# tutorial3.net
KiCad netlist of a schematic drawn in EAGLE
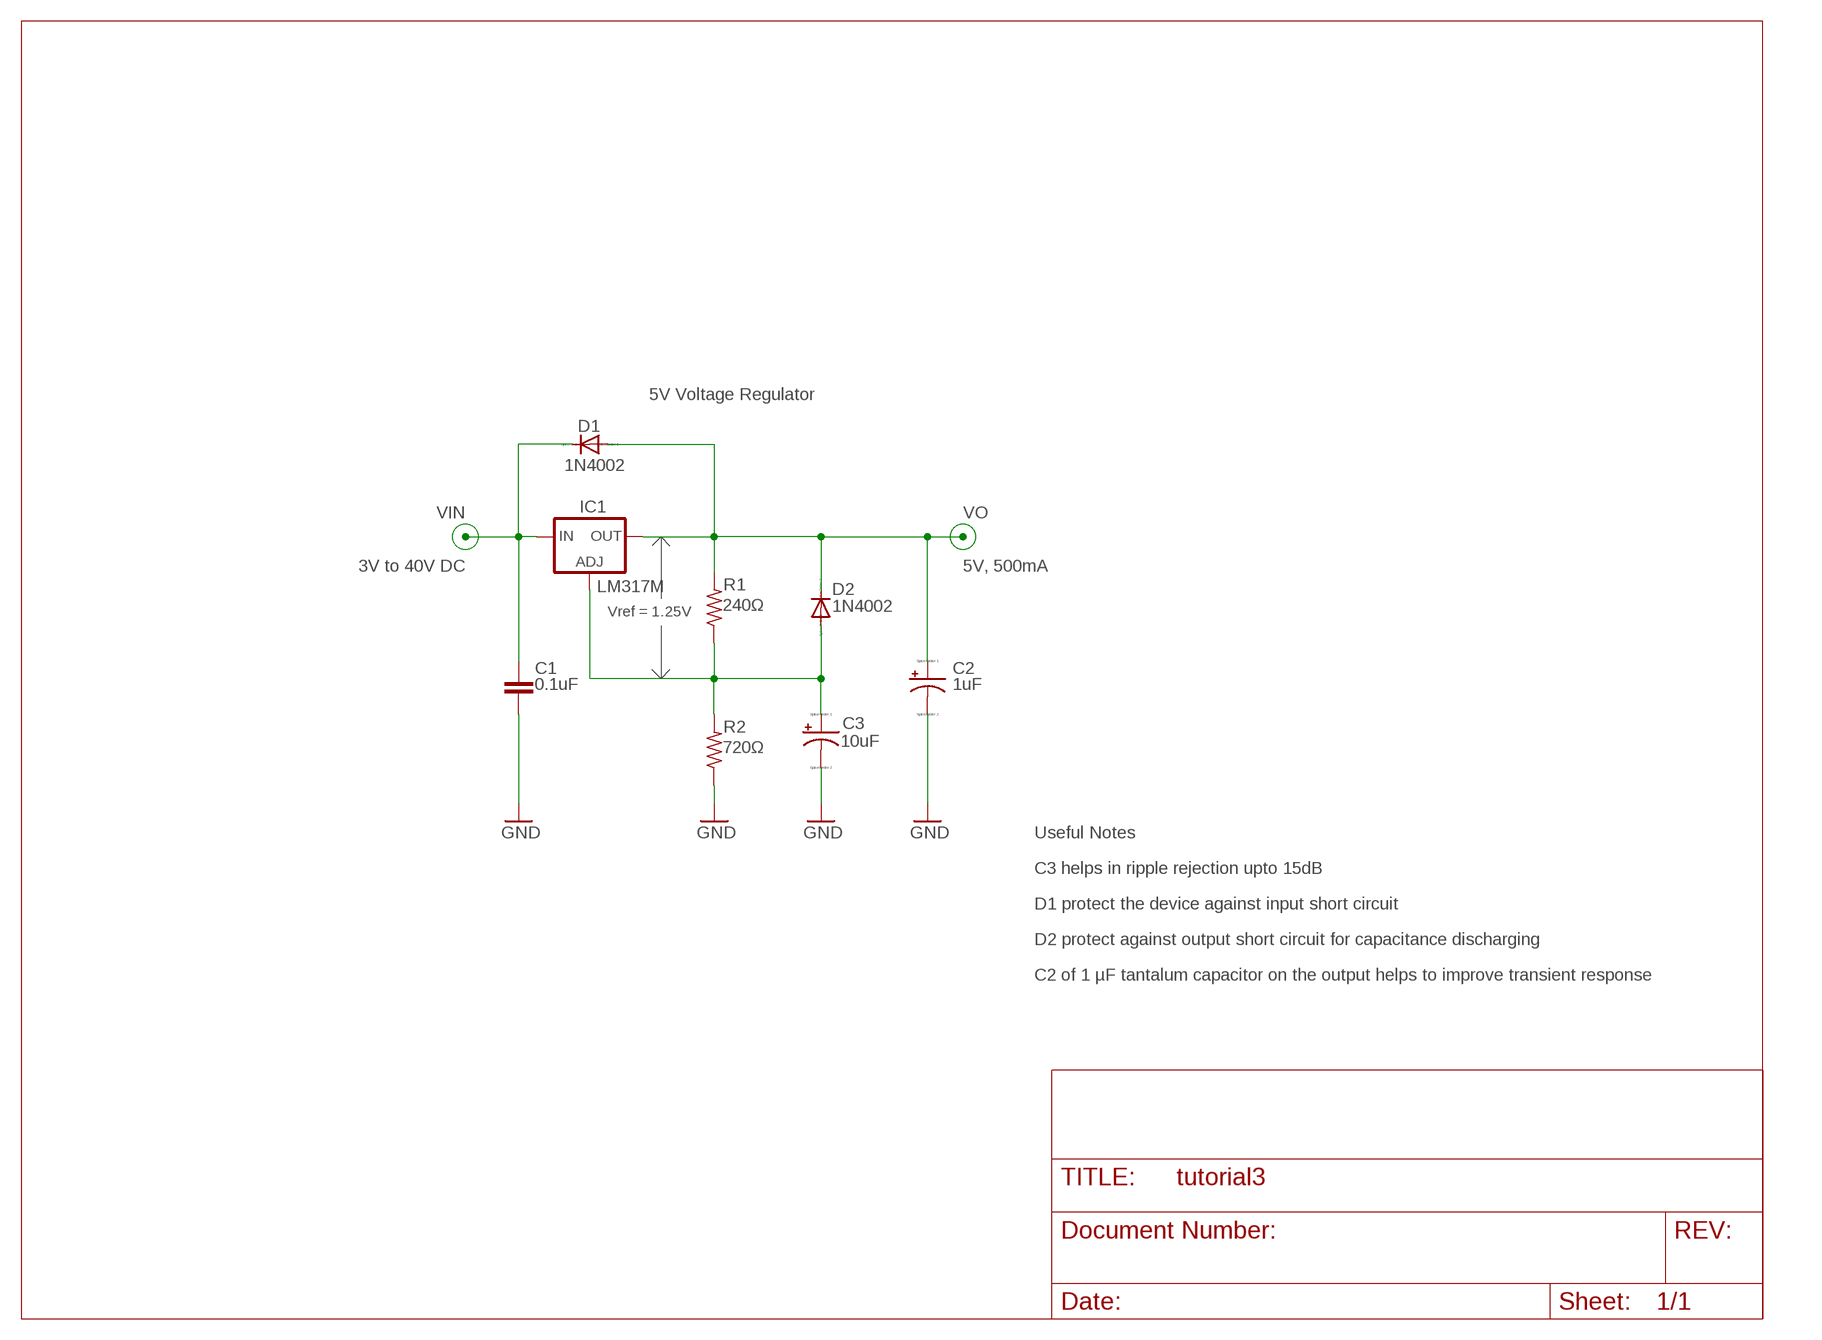
[diagram p0: schematic, sheet 1]

(export (version "E")
  (design (tool "Eeschema 10.0.6"))
  (components
    (comp (ref "C1")
      (value "0.1uF")
      (footprint "eagle-import:C075-052X106")
      (libsource (lib "eagle-import") (part "C-EU075-052X106"))
    )
    (comp (ref "C2")
      (value "1uF")
      (footprint "eagle-import:085CS_1AR")
      (libsource (lib "eagle-import") (part "CPOL-US085CS-1AR"))
    )
    (comp (ref "C3")
      (value "10uF")
      (footprint "eagle-import:085CS_1AR")
      (libsource (lib "eagle-import") (part "CPOL-US085CS-1AR"))
    )
    (comp (ref "D1")
      (value "1N4002")
      (footprint "eagle-import:DO41-10")
      (libsource (lib "eagle-import") (part "1N4004"))
    )
    (comp (ref "D2")
      (value "1N4002")
      (footprint "eagle-import:DO41-10")
      (libsource (lib "eagle-import") (part "1N4004"))
    )
    (comp (ref "IC1")
      (value "LM317MBSTT3")
      (footprint "eagle-import:SOT223")
      (fields (field (name "PARTNUMBER") "LM317M"))
      (libsource (lib "eagle-import") (part "LM317?MBSTT3"))
    )
    (comp (ref "R1")
      (value "240Ω")
      (footprint "eagle-import:M0805")
      (libsource (lib "eagle-import") (part "R-US_M0805"))
    )
    (comp (ref "R2")
      (value "720Ω")
      (footprint "eagle-import:M0805")
      (libsource (lib "eagle-import") (part "R-US_M0805"))
    )
  )
  (nets
    (net (code "1") (name "/VIN") (class "Default")
      (node (ref "C1") (pin "1") (pinfunction "1_1") (pintype "passive"))
      (node (ref "D1") (pin "C") (pinfunction "C_C") (pintype "passive"))
      (node (ref "IC1") (pin "3") (pinfunction "IN_3") (pintype "input"))
    )
    (net (code "2") (name "/VO") (class "Default")
      (node (ref "C2") (pin "+") (pinfunction "+_+") (pintype "passive"))
      (node (ref "D1") (pin "A") (pinfunction "A_A") (pintype "passive"))
      (node (ref "D2") (pin "C") (pinfunction "C_C") (pintype "passive"))
      (node (ref "IC1") (pin "4") (pinfunction "OUT_4") (pintype "passive"))
      (node (ref "R1") (pin "2") (pinfunction "2_2") (pintype "passive"))
    )
    (net (code "3") (name "GND") (class "Default")
      (node (ref "C1") (pin "2") (pinfunction "2_2") (pintype "passive"))
      (node (ref "C2") (pin "-") (pinfunction "-_-") (pintype "passive"))
      (node (ref "C3") (pin "-") (pinfunction "-_-") (pintype "passive"))
      (node (ref "R2") (pin "1") (pinfunction "1_1") (pintype "passive"))
    )
    (net (code "4") (name "Net-(IC1-ADJ)") (class "Default")
      (node (ref "C3") (pin "+") (pinfunction "+_+") (pintype "passive"))
      (node (ref "D2") (pin "A") (pinfunction "A_A") (pintype "passive"))
      (node (ref "IC1") (pin "1") (pinfunction "ADJ_1") (pintype "input"))
      (node (ref "R1") (pin "1") (pinfunction "1_1") (pintype "passive"))
      (node (ref "R2") (pin "2") (pinfunction "2_2") (pintype "passive"))
    )
  )
)
